# mbmc_io.net
KiCad netlist of a schematic drawn in EAGLE
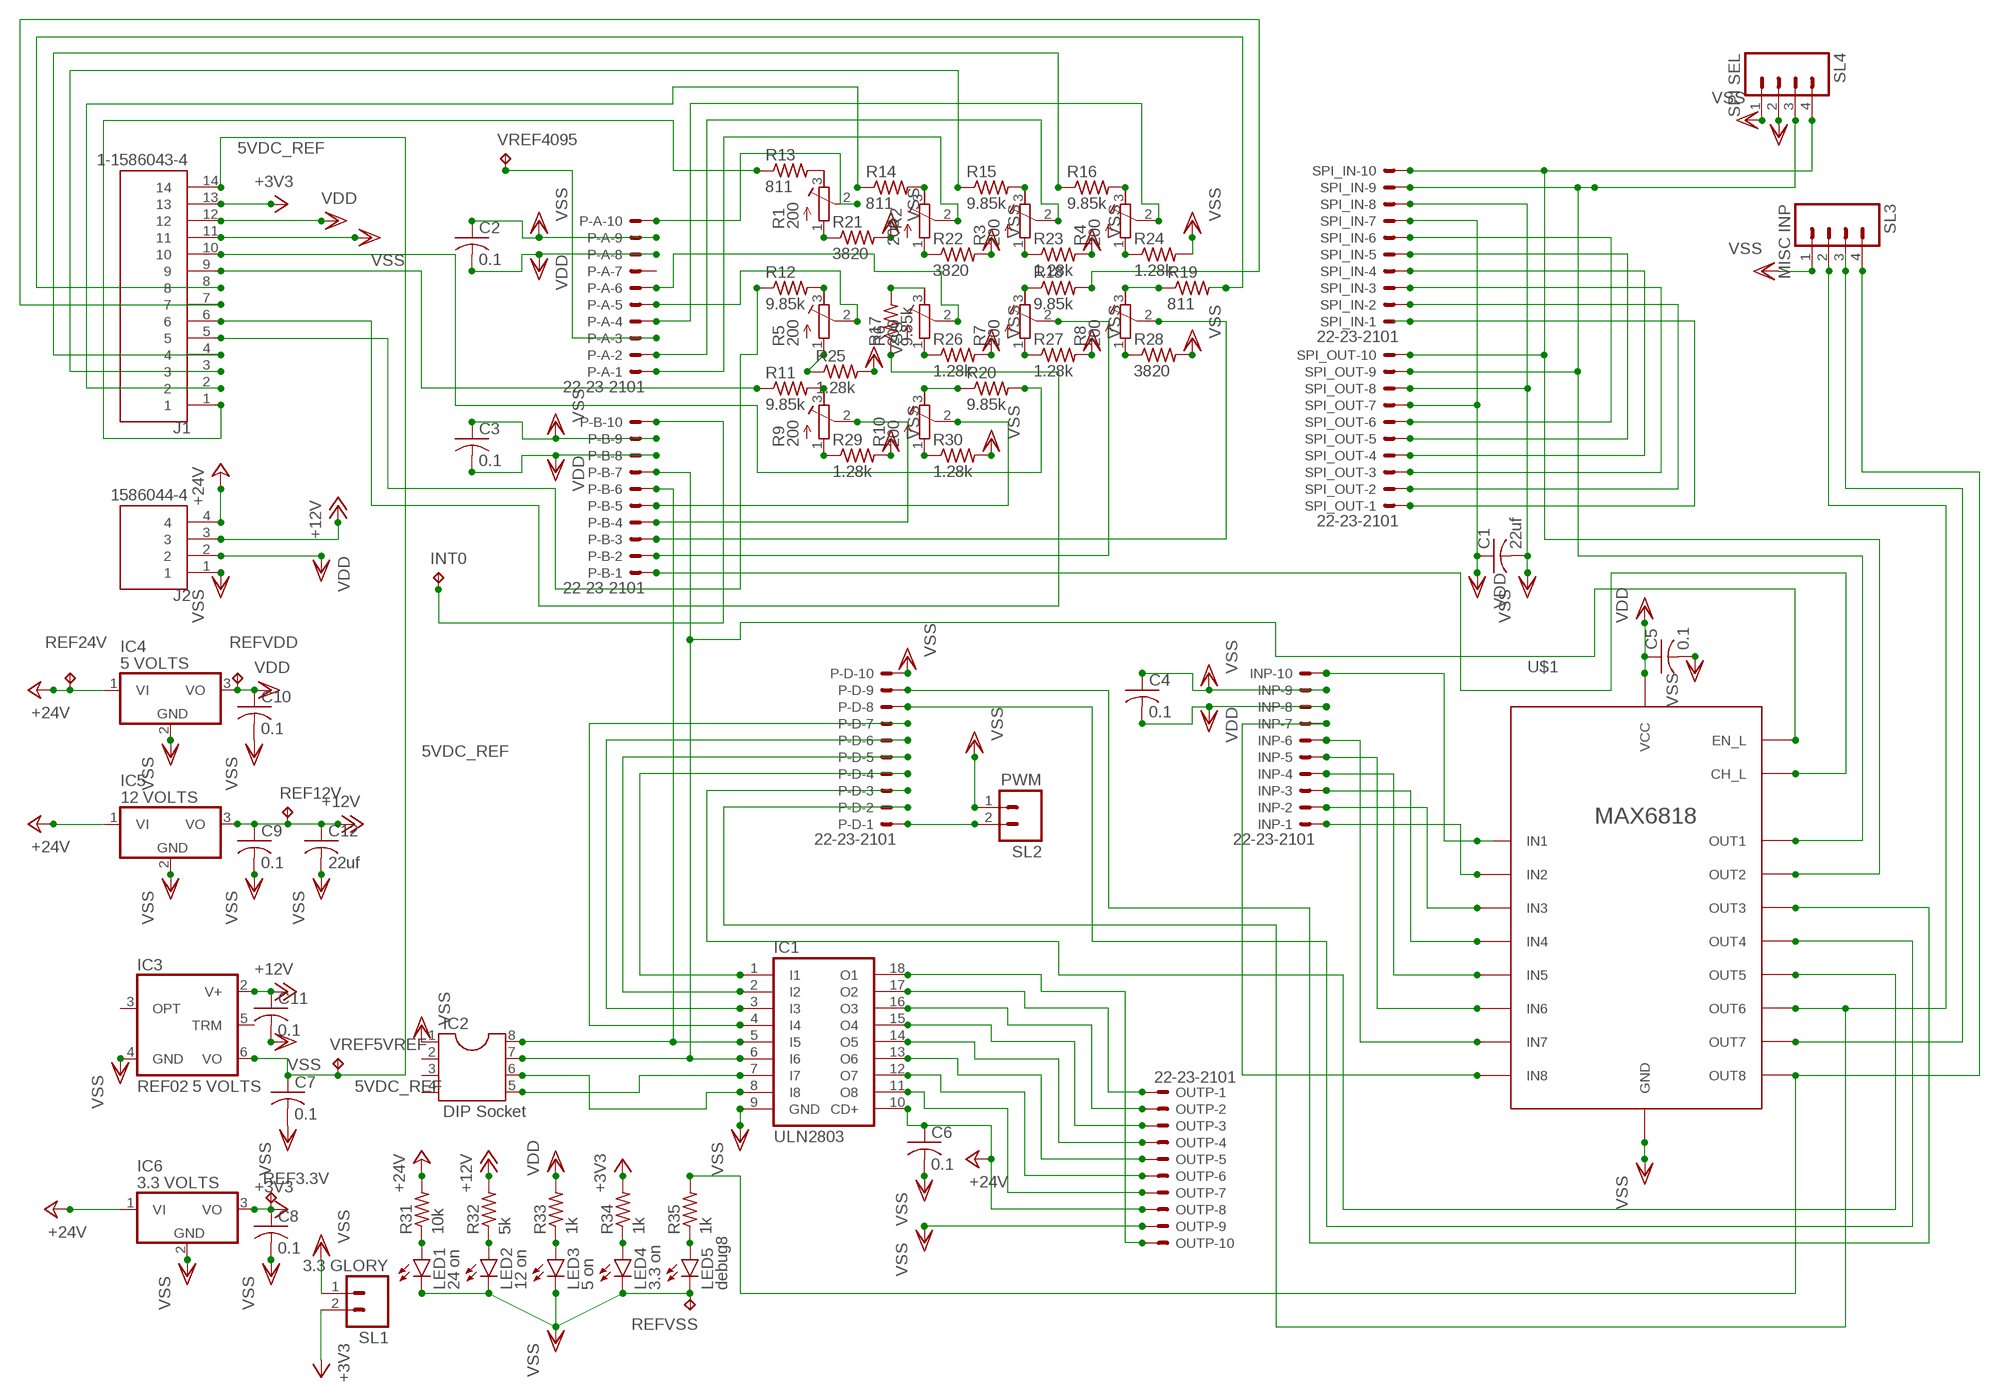
[diagram p0: schematic, sheet 1]

(export (version "E")
  (design (tool "Eeschema 10.0.6"))
  (components
    (comp (ref "C1")
      (value "22uf")
      (footprint "eagle-import:C0805")
      (libsource (lib "eagle-import") (part "C-USC0805"))
    )
    (comp (ref "C2")
      (value "0.1")
      (footprint "eagle-import:C0805")
      (libsource (lib "eagle-import") (part "C-USC0805"))
    )
    (comp (ref "C3")
      (value "0.1")
      (footprint "eagle-import:C0805")
      (libsource (lib "eagle-import") (part "C-USC0805"))
    )
    (comp (ref "C4")
      (value "0.1")
      (footprint "eagle-import:C0805")
      (libsource (lib "eagle-import") (part "C-USC0805"))
    )
    (comp (ref "C5")
      (value "0.1")
      (footprint "eagle-import:C0805")
      (libsource (lib "eagle-import") (part "C-USC0805"))
    )
    (comp (ref "C6")
      (value "0.1")
      (footprint "eagle-import:C0805")
      (libsource (lib "eagle-import") (part "C-USC0805"))
    )
    (comp (ref "C7")
      (value "0.1")
      (footprint "eagle-import:C0805")
      (libsource (lib "eagle-import") (part "C-USC0805"))
    )
    (comp (ref "C8")
      (value "0.1")
      (footprint "eagle-import:C0805")
      (libsource (lib "eagle-import") (part "C-USC0805"))
    )
    (comp (ref "C9")
      (value "0.1")
      (footprint "eagle-import:C0805")
      (libsource (lib "eagle-import") (part "C-USC0805"))
    )
    (comp (ref "C10")
      (value "0.1")
      (footprint "eagle-import:C0805")
      (libsource (lib "eagle-import") (part "C-USC0805"))
    )
    (comp (ref "C11")
      (value "0.1")
      (footprint "eagle-import:C0805")
      (libsource (lib "eagle-import") (part "C-USC0805"))
    )
    (comp (ref "C12")
      (value "22uf")
      (footprint "eagle-import:C0805")
      (libsource (lib "eagle-import") (part "C-USC0805"))
    )
    (comp (ref "IC1")
      (value "ULN2803")
      (footprint "eagle-import:DIL18")
      (libsource (lib "eagle-import") (part "ULN2803A"))
    )
    (comp (ref "IC2")
      (value "DIP Socket")
      (footprint "eagle-import:SOCKET-08")
      (libsource (lib "eagle-import") (part "DIL8S"))
    )
    (comp (ref "IC3")
      (value "REF02 5 VOLTS")
      (footprint "eagle-import:DIL08")
      (libsource (lib "eagle-import") (part "REF02Z"))
    )
    (comp (ref "IC4")
      (value "5 VOLTS")
      (footprint "eagle-import:TO220V")
      (libsource (lib "eagle-import") (part "78TV05"))
    )
    (comp (ref "IC5")
      (value "12 VOLTS")
      (footprint "eagle-import:TO220V")
      (libsource (lib "eagle-import") (part "78TV05"))
    )
    (comp (ref "IC6")
      (value "3.3 VOLTS")
      (footprint "eagle-import:TO220V")
      (libsource (lib "eagle-import") (part "78TV05"))
    )
    (comp (ref "INP")
      (value "22-23-2101")
      (footprint "eagle-import:22-23-2101")
      (fields (field (name "MF") "MOLEX"))
      (libsource (lib "eagle-import") (part "22-23-2101"))
    )
    (comp (ref "INT0")
      (value "TPB1,27")
      (footprint "eagle-import:B1,27")
      (libsource (lib "eagle-import") (part "TPB1,27"))
    )
    (comp (ref "J1")
      (value "1-1586043-4")
      (footprint "eagle-import:TE_1-1586043-4")
      (fields (field (name "MANUFACTURER") "TE"))
      (libsource (lib "eagle-import") (part "1-1586043-4"))
    )
    (comp (ref "J2")
      (value "1586044-4")
      (footprint "eagle-import:TE_1586044-4")
      (fields (field (name "MANUFACTURER") "TE"))
      (libsource (lib "eagle-import") (part "1586044-4"))
    )
    (comp (ref "LED1")
      (value "24 on")
      (footprint "eagle-import:CHIPLED_1206")
      (libsource (lib "eagle-import") (part "LEDCHIPLED_1206"))
    )
    (comp (ref "LED2")
      (value "12 on")
      (footprint "eagle-import:CHIPLED_1206")
      (libsource (lib "eagle-import") (part "LEDCHIPLED_1206"))
    )
    (comp (ref "LED3")
      (value "5 on")
      (footprint "eagle-import:CHIPLED_1206")
      (libsource (lib "eagle-import") (part "LEDCHIPLED_1206"))
    )
    (comp (ref "LED4")
      (value "3.3 on")
      (footprint "eagle-import:CHIPLED_1206")
      (libsource (lib "eagle-import") (part "LEDCHIPLED_1206"))
    )
    (comp (ref "LED5")
      (value "debug8")
      (footprint "eagle-import:CHIPLED_1206")
      (libsource (lib "eagle-import") (part "LEDCHIPLED_1206"))
    )
    (comp (ref "OUTP")
      (value "22-23-2101")
      (footprint "eagle-import:22-23-2101")
      (fields (field (name "MF") "MOLEX"))
      (libsource (lib "eagle-import") (part "22-23-2101"))
    )
    (comp (ref "P-A")
      (value "22-23-2101")
      (footprint "eagle-import:22-23-2101")
      (fields (field (name "MF") "MOLEX"))
      (libsource (lib "eagle-import") (part "22-23-2101"))
    )
    (comp (ref "P-B")
      (value "22-23-2101")
      (footprint "eagle-import:22-23-2101")
      (fields (field (name "MF") "MOLEX"))
      (libsource (lib "eagle-import") (part "22-23-2101"))
    )
    (comp (ref "P-D")
      (value "22-23-2101")
      (footprint "eagle-import:22-23-2101")
      (fields (field (name "MF") "MOLEX"))
      (libsource (lib "eagle-import") (part "22-23-2101"))
    )
    (comp (ref "R1")
      (value "200")
      (footprint "eagle-import:RTRIM3339P")
      (libsource (lib "eagle-import") (part "R-TRIMM3339P"))
    )
    (comp (ref "R2")
      (value "200")
      (footprint "eagle-import:RTRIM3339P")
      (libsource (lib "eagle-import") (part "R-TRIMM3339P"))
    )
    (comp (ref "R3")
      (value "200")
      (footprint "eagle-import:RTRIM3339P")
      (libsource (lib "eagle-import") (part "R-TRIMM3339P"))
    )
    (comp (ref "R4")
      (value "200")
      (footprint "eagle-import:RTRIM3339P")
      (libsource (lib "eagle-import") (part "R-TRIMM3339P"))
    )
    (comp (ref "R5")
      (value "200")
      (footprint "eagle-import:RTRIM3339P")
      (libsource (lib "eagle-import") (part "R-TRIMM3339P"))
    )
    (comp (ref "R6")
      (value "200")
      (footprint "eagle-import:RTRIM3339P")
      (libsource (lib "eagle-import") (part "R-TRIMM3339P"))
    )
    (comp (ref "R7")
      (value "200")
      (footprint "eagle-import:RTRIM3339P")
      (libsource (lib "eagle-import") (part "R-TRIMM3339P"))
    )
    (comp (ref "R8")
      (value "200")
      (footprint "eagle-import:RTRIM3339P")
      (libsource (lib "eagle-import") (part "R-TRIMM3339P"))
    )
    (comp (ref "R9")
      (value "200")
      (footprint "eagle-import:RTRIM3339P")
      (libsource (lib "eagle-import") (part "R-TRIMM3339P"))
    )
    (comp (ref "R10")
      (value "200")
      (footprint "eagle-import:RTRIM3339P")
      (libsource (lib "eagle-import") (part "R-TRIMM3339P"))
    )
    (comp (ref "R11")
      (value "9.85k")
      (footprint "eagle-import:R0805")
      (libsource (lib "eagle-import") (part "R-US_R0805"))
    )
    (comp (ref "R12")
      (value "9.85k")
      (footprint "eagle-import:R0805")
      (libsource (lib "eagle-import") (part "R-US_R0805"))
    )
    (comp (ref "R13")
      (value "811")
      (footprint "eagle-import:R0805")
      (libsource (lib "eagle-import") (part "R-US_R0805"))
    )
    (comp (ref "R14")
      (value "811")
      (footprint "eagle-import:R0805")
      (libsource (lib "eagle-import") (part "R-US_R0805"))
    )
    (comp (ref "R15")
      (value "9.85k")
      (footprint "eagle-import:R0805")
      (libsource (lib "eagle-import") (part "R-US_R0805"))
    )
    (comp (ref "R16")
      (value "9.85k")
      (footprint "eagle-import:R0805")
      (libsource (lib "eagle-import") (part "R-US_R0805"))
    )
    (comp (ref "R17")
      (value "9.85k")
      (footprint "eagle-import:R0805")
      (libsource (lib "eagle-import") (part "R-US_R0805"))
    )
    (comp (ref "R18")
      (value "9.85k")
      (footprint "eagle-import:R0805")
      (libsource (lib "eagle-import") (part "R-US_R0805"))
    )
    (comp (ref "R19")
      (value "811")
      (footprint "eagle-import:R0805")
      (libsource (lib "eagle-import") (part "R-US_R0805"))
    )
    (comp (ref "R20")
      (value "9.85k")
      (footprint "eagle-import:R0805")
      (libsource (lib "eagle-import") (part "R-US_R0805"))
    )
    (comp (ref "R21")
      (value "3820")
      (footprint "eagle-import:R0805")
      (libsource (lib "eagle-import") (part "R-US_R0805"))
    )
    (comp (ref "R22")
      (value "3820")
      (footprint "eagle-import:R0805")
      (libsource (lib "eagle-import") (part "R-US_R0805"))
    )
    (comp (ref "R23")
      (value "1.28k")
      (footprint "eagle-import:R0805")
      (libsource (lib "eagle-import") (part "R-US_R0805"))
    )
    (comp (ref "R24")
      (value "1.28k")
      (footprint "eagle-import:R0805")
      (libsource (lib "eagle-import") (part "R-US_R0805"))
    )
    (comp (ref "R25")
      (value "1.28k")
      (footprint "eagle-import:R0805")
      (libsource (lib "eagle-import") (part "R-US_R0805"))
    )
    (comp (ref "R26")
      (value "1.28k")
      (footprint "eagle-import:R0805")
      (libsource (lib "eagle-import") (part "R-US_R0805"))
    )
    (comp (ref "R27")
      (value "1.28k")
      (footprint "eagle-import:R0805")
      (libsource (lib "eagle-import") (part "R-US_R0805"))
    )
    (comp (ref "R28")
      (value "3820")
      (footprint "eagle-import:R0805")
      (libsource (lib "eagle-import") (part "R-US_R0805"))
    )
    (comp (ref "R29")
      (value "1.28k")
      (footprint "eagle-import:R0805")
      (libsource (lib "eagle-import") (part "R-US_R0805"))
    )
    (comp (ref "R30")
      (value "1.28k")
      (footprint "eagle-import:R0805")
      (libsource (lib "eagle-import") (part "R-US_R0805"))
    )
    (comp (ref "R31")
      (value "10k")
      (footprint "eagle-import:R0805")
      (libsource (lib "eagle-import") (part "R-US_R0805"))
    )
    (comp (ref "R32")
      (value "5k")
      (footprint "eagle-import:R0805")
      (libsource (lib "eagle-import") (part "R-US_R0805"))
    )
    (comp (ref "R33")
      (value "1k")
      (footprint "eagle-import:R0805")
      (libsource (lib "eagle-import") (part "R-US_R0805"))
    )
    (comp (ref "R34")
      (value "1k")
      (footprint "eagle-import:R0805")
      (libsource (lib "eagle-import") (part "R-US_R0805"))
    )
    (comp (ref "R35")
      (value "1k")
      (footprint "eagle-import:R0805")
      (libsource (lib "eagle-import") (part "R-US_R0805"))
    )
    (comp (ref "REF3.3V")
      (value "TPB1,27")
      (footprint "eagle-import:B1,27")
      (libsource (lib "eagle-import") (part "TPB1,27"))
    )
    (comp (ref "REF12V")
      (value "TPB1,27")
      (footprint "eagle-import:B1,27")
      (libsource (lib "eagle-import") (part "TPB1,27"))
    )
    (comp (ref "REF24V")
      (value "TPB1,27")
      (footprint "eagle-import:B1,27")
      (libsource (lib "eagle-import") (part "TPB1,27"))
    )
    (comp (ref "REFVDD")
      (value "TPB1,27")
      (footprint "eagle-import:B1,27")
      (libsource (lib "eagle-import") (part "TPB1,27"))
    )
    (comp (ref "REFVSS")
      (value "TPB1,27")
      (footprint "eagle-import:B1,27")
      (libsource (lib "eagle-import") (part "TPB1,27"))
    )
    (comp (ref "SL1")
      (value "3.3 GLORY")
      (footprint "eagle-import:02P")
      (libsource (lib "eagle-import") (part "M02"))
    )
    (comp (ref "SL2")
      (value "PWM")
      (footprint "eagle-import:02P")
      (libsource (lib "eagle-import") (part "M02"))
    )
    (comp (ref "SL3")
      (value "MISC INP")
      (footprint "eagle-import:04P")
      (libsource (lib "eagle-import") (part "M04"))
    )
    (comp (ref "SL4")
      (value "SPI SEL")
      (footprint "eagle-import:04P")
      (libsource (lib "eagle-import") (part "M04"))
    )
    (comp (ref "SPI_IN")
      (value "22-23-2101")
      (footprint "eagle-import:22-23-2101")
      (fields (field (name "MF") "MOLEX"))
      (libsource (lib "eagle-import") (part "22-23-2101"))
    )
    (comp (ref "SPI_OUT")
      (value "22-23-2101")
      (footprint "eagle-import:22-23-2101")
      (fields (field (name "MF") "MOLEX"))
      (libsource (lib "eagle-import") (part "22-23-2101"))
    )
    (comp (ref "U$1")
      (value "MAX6818")
      (footprint "eagle-import:SSOP20")
      (fields (field (name "MF") "Maxim Integrated"))
      (libsource (lib "eagle-import") (part "MAX6818"))
    )
    (comp (ref "VREF5VREF")
      (value "TPB1,27")
      (footprint "eagle-import:B1,27")
      (libsource (lib "eagle-import") (part "TPB1,27"))
    )
    (comp (ref "VREF4095")
      (value "TPB1,27")
      (footprint "eagle-import:B1,27")
      (libsource (lib "eagle-import") (part "TPB1,27"))
    )
  )
  (nets
    (net (code "1") (name "+3V3") (class "Default")
      (node (ref "C8") (pin "1") (pinfunction "1_1") (pintype "passive"))
      (node (ref "IC6") (pin "3") (pinfunction "VO_3") (pintype "passive"))
      (node (ref "J1") (pin "13") (pinfunction "13_13") (pintype "passive"))
      (node (ref "R34") (pin "2") (pinfunction "2_2") (pintype "passive"))
      (node (ref "REF3.3V") (pin "TP") (pinfunction "TP_TP") (pintype "input"))
      (node (ref "SL1") (pin "2") (pinfunction "2_2") (pintype "passive"))
    )
    (net (code "2") (name "+12V") (class "Default")
      (node (ref "C11") (pin "1") (pinfunction "1_1") (pintype "passive"))
      (node (ref "C12") (pin "1") (pinfunction "1_1") (pintype "passive"))
      (node (ref "C9") (pin "1") (pinfunction "1_1") (pintype "passive"))
      (node (ref "IC3") (pin "2") (pinfunction "V+_2") (pintype "power_in"))
      (node (ref "IC5") (pin "3") (pinfunction "VO_3") (pintype "passive"))
      (node (ref "J2") (pin "3") (pinfunction "3_3") (pintype "passive"))
      (node (ref "R32") (pin "2") (pinfunction "2_2") (pintype "passive"))
      (node (ref "REF12V") (pin "TP") (pinfunction "TP_TP") (pintype "input"))
    )
    (net (code "3") (name "+24V") (class "Default")
      (node (ref "C6") (pin "1") (pinfunction "1_1") (pintype "passive"))
      (node (ref "IC1") (pin "10") (pinfunction "CD+_10") (pintype "passive"))
      (node (ref "IC4") (pin "1") (pinfunction "VI_1") (pintype "input"))
      (node (ref "IC5") (pin "1") (pinfunction "VI_1") (pintype "input"))
      (node (ref "IC6") (pin "1") (pinfunction "VI_1") (pintype "input"))
      (node (ref "J2") (pin "4") (pinfunction "4_4") (pintype "passive"))
      (node (ref "OUTP") (pin "8") (pinfunction "S_8") (pintype "passive"))
      (node (ref "R31") (pin "2") (pinfunction "2_2") (pintype "passive"))
      (node (ref "REF24V") (pin "TP") (pinfunction "TP_TP") (pintype "input"))
    )
    (net (code "4") (name "/5VDC_REF") (class "Default")
      (node (ref "C7") (pin "1") (pinfunction "1_1") (pintype "passive"))
      (node (ref "IC3") (pin "6") (pinfunction "VO_6") (pintype "output"))
      (node (ref "J1") (pin "14") (pinfunction "14_14") (pintype "passive"))
      (node (ref "VREF5VREF") (pin "TP") (pinfunction "TP_TP") (pintype "input"))
    )
    (net (code "5") (name "Net-(IC1-I1)") (class "Default")
      (node (ref "IC1") (pin "1") (pinfunction "I1_1") (pintype "input"))
      (node (ref "P-D") (pin "4") (pinfunction "S_4") (pintype "passive"))
    )
    (net (code "6") (name "Net-(IC1-I2)") (class "Default")
      (node (ref "IC1") (pin "2") (pinfunction "I2_2") (pintype "input"))
      (node (ref "P-D") (pin "5") (pinfunction "S_5") (pintype "passive"))
    )
    (net (code "7") (name "Net-(IC1-I3)") (class "Default")
      (node (ref "IC1") (pin "3") (pinfunction "I3_3") (pintype "input"))
      (node (ref "P-D") (pin "6") (pinfunction "S_6") (pintype "passive"))
    )
    (net (code "8") (name "Net-(IC1-I4)") (class "Default")
      (node (ref "IC1") (pin "4") (pinfunction "I4_4") (pintype "input"))
      (node (ref "P-D") (pin "7") (pinfunction "S_7") (pintype "passive"))
    )
    (net (code "9") (name "Net-(IC1-I5)") (class "Default")
      (node (ref "IC1") (pin "5") (pinfunction "I5_5") (pintype "input"))
      (node (ref "IC2") (pin "8") (pinfunction "8_8") (pintype "passive"))
      (node (ref "P-B") (pin "6") (pinfunction "S_6") (pintype "passive"))
    )
    (net (code "10") (name "Net-(IC1-I6)") (class "Default")
      (node (ref "IC1") (pin "6") (pinfunction "I6_6") (pintype "input"))
      (node (ref "IC2") (pin "7") (pinfunction "7_7") (pintype "passive"))
      (node (ref "P-B") (pin "7") (pinfunction "S_7") (pintype "passive"))
      (node (ref "U$1") (pin "EN_L") (pinfunction "EN_L_EN_L") (pintype "bidirectional"))
    )
    (net (code "11") (name "Net-(IC1-I7)") (class "Default")
      (node (ref "IC1") (pin "7") (pinfunction "I7_7") (pintype "input"))
      (node (ref "IC2") (pin "5") (pinfunction "5_5") (pintype "passive"))
    )
    (net (code "12") (name "Net-(IC1-I8)") (class "Default")
      (node (ref "IC1") (pin "8") (pinfunction "I8_8") (pintype "input"))
      (node (ref "IC2") (pin "6") (pinfunction "6_6") (pintype "passive"))
    )
    (net (code "13") (name "Net-(IC1-O1)") (class "Default")
      (node (ref "IC1") (pin "18") (pinfunction "O1_18") (pintype "open_collector"))
      (node (ref "OUTP") (pin "10") (pinfunction "S_10") (pintype "passive"))
    )
    (net (code "14") (name "Net-(IC1-O2)") (class "Default")
      (node (ref "IC1") (pin "17") (pinfunction "O2_17") (pintype "open_collector"))
      (node (ref "OUTP") (pin "1") (pinfunction "S_1") (pintype "passive"))
    )
    (net (code "15") (name "Net-(IC1-O3)") (class "Default")
      (node (ref "IC1") (pin "16") (pinfunction "O3_16") (pintype "open_collector"))
      (node (ref "OUTP") (pin "2") (pinfunction "S_2") (pintype "passive"))
    )
    (net (code "16") (name "Net-(IC1-O4)") (class "Default")
      (node (ref "IC1") (pin "15") (pinfunction "O4_15") (pintype "open_collector"))
      (node (ref "OUTP") (pin "3") (pinfunction "S_3") (pintype "passive"))
    )
    (net (code "17") (name "Net-(IC1-O5)") (class "Default")
      (node (ref "IC1") (pin "14") (pinfunction "O5_14") (pintype "open_collector"))
      (node (ref "OUTP") (pin "4") (pinfunction "S_4") (pintype "passive"))
    )
    (net (code "18") (name "Net-(IC1-O6)") (class "Default")
      (node (ref "IC1") (pin "13") (pinfunction "O6_13") (pintype "open_collector"))
      (node (ref "OUTP") (pin "5") (pinfunction "S_5") (pintype "passive"))
    )
    (net (code "19") (name "Net-(IC1-O7)") (class "Default")
      (node (ref "IC1") (pin "12") (pinfunction "O7_12") (pintype "open_collector"))
      (node (ref "OUTP") (pin "6") (pinfunction "S_6") (pintype "passive"))
    )
    (net (code "20") (name "Net-(IC1-O8)") (class "Default")
      (node (ref "IC1") (pin "11") (pinfunction "O8_11") (pintype "open_collector"))
      (node (ref "OUTP") (pin "7") (pinfunction "S_7") (pintype "passive"))
    )
    (net (code "21") (name "Net-(INPA-S)") (class "Default")
      (node (ref "INP") (pin "1") (pinfunction "S_1") (pintype "passive"))
      (node (ref "U$1") (pin "IN2") (pinfunction "IN2_IN2") (pintype "bidirectional"))
    )
    (net (code "22") (name "Net-(INPB-S)") (class "Default")
      (node (ref "INP") (pin "10") (pinfunction "S_10") (pintype "passive"))
      (node (ref "U$1") (pin "IN1") (pinfunction "IN1_IN1") (pintype "bidirectional"))
    )
    (net (code "23") (name "Net-(INPC-S)") (class "Default")
      (node (ref "INP") (pin "2") (pinfunction "S_2") (pintype "passive"))
      (node (ref "U$1") (pin "IN3") (pinfunction "IN3_IN3") (pintype "bidirectional"))
    )
    (net (code "24") (name "Net-(INPD-S)") (class "Default")
      (node (ref "INP") (pin "3") (pinfunction "S_3") (pintype "passive"))
      (node (ref "U$1") (pin "IN4") (pinfunction "IN4_IN4") (pintype "bidirectional"))
    )
    (net (code "25") (name "Net-(INPE-S)") (class "Default")
      (node (ref "INP") (pin "4") (pinfunction "S_4") (pintype "passive"))
      (node (ref "U$1") (pin "IN5") (pinfunction "IN5_IN5") (pintype "bidirectional"))
    )
    (net (code "26") (name "Net-(INPF-S)") (class "Default")
      (node (ref "INP") (pin "5") (pinfunction "S_5") (pintype "passive"))
      (node (ref "U$1") (pin "IN6") (pinfunction "IN6_IN6") (pintype "bidirectional"))
    )
    (net (code "27") (name "Net-(INPG-S)") (class "Default")
      (node (ref "INP") (pin "6") (pinfunction "S_6") (pintype "passive"))
      (node (ref "U$1") (pin "IN7") (pinfunction "IN7_IN7") (pintype "bidirectional"))
    )
    (net (code "28") (name "Net-(INPH-S)") (class "Default")
      (node (ref "INP") (pin "7") (pinfunction "S_7") (pintype "passive"))
      (node (ref "U$1") (pin "IN8") (pinfunction "IN8_IN8") (pintype "bidirectional"))
    )
    (net (code "29") (name "Net-(J1-Pad1)") (class "Default")
      (node (ref "J1") (pin "1") (pinfunction "1_1") (pintype "passive"))
      (node (ref "R13") (pin "1") (pinfunction "1_1") (pintype "passive"))
    )
    (net (code "30") (name "Net-(J1-Pad2)") (class "Default")
      (node (ref "J1") (pin "2") (pinfunction "2_2") (pintype "passive"))
      (node (ref "R14") (pin "1") (pinfunction "1_1") (pintype "passive"))
    )
    (net (code "31") (name "Net-(J1-Pad3)") (class "Default")
      (node (ref "J1") (pin "3") (pinfunction "3_3") (pintype "passive"))
      (node (ref "R15") (pin "1") (pinfunction "1_1") (pintype "passive"))
    )
    (net (code "32") (name "Net-(J1-Pad4)") (class "Default")
      (node (ref "J1") (pin "4") (pinfunction "4_4") (pintype "passive"))
      (node (ref "R16") (pin "1") (pinfunction "1_1") (pintype "passive"))
    )
    (net (code "33") (name "Net-(J1-Pad5)") (class "Default")
      (node (ref "J1") (pin "5") (pinfunction "5_5") (pintype "passive"))
      (node (ref "R12") (pin "1") (pinfunction "1_1") (pintype "passive"))
    )
    (net (code "34") (name "Net-(J1-Pad6)") (class "Default")
      (node (ref "J1") (pin "6") (pinfunction "6_6") (pintype "passive"))
      (node (ref "R17") (pin "1") (pinfunction "1_1") (pintype "passive"))
    )
    (net (code "35") (name "Net-(J1-Pad7)") (class "Default")
      (node (ref "J1") (pin "7") (pinfunction "7_7") (pintype "passive"))
      (node (ref "R18") (pin "2") (pinfunction "2_2") (pintype "passive"))
    )
    (net (code "36") (name "Net-(J1-Pad8)") (class "Default")
      (node (ref "J1") (pin "8") (pinfunction "8_8") (pintype "passive"))
      (node (ref "R19") (pin "2") (pinfunction "2_2") (pintype "passive"))
    )
    (net (code "37") (name "Net-(J1-Pad9)") (class "Default")
      (node (ref "J1") (pin "9") (pinfunction "9_9") (pintype "passive"))
      (node (ref "R11") (pin "1") (pinfunction "1_1") (pintype "passive"))
    )
    (net (code "38") (name "Net-(J1-Pad10)") (class "Default")
      (node (ref "J1") (pin "10") (pinfunction "10_10") (pintype "passive"))
      (node (ref "R20") (pin "2") (pinfunction "2_2") (pintype "passive"))
    )
    (net (code "39") (name "Net-(LED1-PadA)") (class "Default")
      (node (ref "LED1") (pin "A") (pinfunction "A_A") (pintype "passive"))
      (node (ref "R31") (pin "1") (pinfunction "1_1") (pintype "passive"))
    )
    (net (code "40") (name "Net-(LED2-PadA)") (class "Default")
      (node (ref "LED2") (pin "A") (pinfunction "A_A") (pintype "passive"))
      (node (ref "R32") (pin "1") (pinfunction "1_1") (pintype "passive"))
    )
    (net (code "41") (name "Net-(LED3-PadA)") (class "Default")
      (node (ref "LED3") (pin "A") (pinfunction "A_A") (pintype "passive"))
      (node (ref "R33") (pin "1") (pinfunction "1_1") (pintype "passive"))
    )
    (net (code "42") (name "Net-(LED4-PadA)") (class "Default")
      (node (ref "LED4") (pin "A") (pinfunction "A_A") (pintype "passive"))
      (node (ref "R34") (pin "1") (pinfunction "1_1") (pintype "passive"))
    )
    (net (code "43") (name "Net-(LED5-PadA)") (class "Default")
      (node (ref "LED5") (pin "A") (pinfunction "A_A") (pintype "passive"))
      (node (ref "R35") (pin "1") (pinfunction "1_1") (pintype "passive"))
    )
    (net (code "44") (name "Net-(P-AA-S)") (class "Default")
      (node (ref "P-A") (pin "1") (pinfunction "S_1") (pintype "passive"))
      (node (ref "R2") (pin "2") (pinfunction "S_2") (pintype "passive"))
    )
    (net (code "45") (name "Net-(P-AB-S)") (class "Default")
      (node (ref "P-A") (pin "10") (pinfunction "S_10") (pintype "passive"))
      (node (ref "R1") (pin "2") (pinfunction "S_2") (pintype "passive"))
    )
    (net (code "46") (name "Net-(P-AC-S)") (class "Default")
      (node (ref "P-A") (pin "2") (pinfunction "S_2") (pintype "passive"))
      (node (ref "R3") (pin "2") (pinfunction "S_2") (pintype "passive"))
    )
    (net (code "47") (name "Net-(P-AD-S)") (class "Default")
      (node (ref "P-A") (pin "3") (pinfunction "S_3") (pintype "passive"))
      (node (ref "VREF4095") (pin "TP") (pinfunction "TP_TP") (pintype "input"))
    )
    (net (code "48") (name "Net-(P-AE-S)") (class "Default")
      (node (ref "P-A") (pin "4") (pinfunction "S_4") (pintype "passive"))
      (node (ref "R4") (pin "2") (pinfunction "S_2") (pintype "passive"))
    )
    (net (code "49") (name "Net-(P-AF-S)") (class "Default")
      (node (ref "P-A") (pin "5") (pinfunction "S_5") (pintype "passive"))
      (node (ref "R5") (pin "2") (pinfunction "S_2") (pintype "passive"))
    )
    (net (code "50") (name "Net-(P-AG-S)") (class "Default")
      (node (ref "P-A") (pin "6") (pinfunction "S_6") (pintype "passive"))
      (node (ref "R6") (pin "2") (pinfunction "S_2") (pintype "passive"))
    )
    (net (code "51") (name "Net-(P-BA-S)") (class "Default")
      (node (ref "P-B") (pin "1") (pinfunction "S_1") (pintype "passive"))
      (node (ref "U$1") (pin "CH_L") (pinfunction "CH_L_CH_L") (pintype "bidirectional"))
    )
    (net (code "52") (name "Net-(P-BB-S)") (class "Default")
      (node (ref "INT0") (pin "TP") (pinfunction "TP_TP") (pintype "input"))
      (node (ref "P-B") (pin "10") (pinfunction "S_10") (pintype "passive"))
    )
    (net (code "53") (name "Net-(P-BC-S)") (class "Default")
      (node (ref "P-B") (pin "2") (pinfunction "S_2") (pintype "passive"))
      (node (ref "R7") (pin "2") (pinfunction "S_2") (pintype "passive"))
    )
    (net (code "54") (name "Net-(P-BD-S)") (class "Default")
      (node (ref "P-B") (pin "3") (pinfunction "S_3") (pintype "passive"))
      (node (ref "R8") (pin "2") (pinfunction "S_2") (pintype "passive"))
    )
    (net (code "55") (name "Net-(P-BE-S)") (class "Default")
      (node (ref "P-B") (pin "4") (pinfunction "S_4") (pintype "passive"))
      (node (ref "R9") (pin "2") (pinfunction "S_2") (pintype "passive"))
    )
    (net (code "56") (name "Net-(P-BF-S)") (class "Default")
      (node (ref "P-B") (pin "5") (pinfunction "S_5") (pintype "passive"))
      (node (ref "R10") (pin "2") (pinfunction "S_2") (pintype "passive"))
    )
    (net (code "57") (name "Net-(P-DA-S)") (class "Default")
      (node (ref "P-D") (pin "1") (pinfunction "S_1") (pintype "passive"))
      (node (ref "SL2") (pin "2") (pinfunction "2_2") (pintype "passive"))
    )
    (net (code "58") (name "Net-(P-DC-S)") (class "Default")
      (node (ref "P-D") (pin "2") (pinfunction "S_2") (pintype "passive"))
      (node (ref "SL3") (pin "2") (pinfunction "2_2") (pintype "passive"))
      (node (ref "U$1") (pin "OUT6") (pinfunction "OUT6_OUT6") (pintype "bidirectional"))
    )
    (net (code "59") (name "Net-(P-DD-S)") (class "Default")
      (node (ref "P-D") (pin "3") (pinfunction "S_3") (pintype "passive"))
      (node (ref "U$1") (pin "OUT5") (pinfunction "OUT5_OUT5") (pintype "bidirectional"))
    )
    (net (code "60") (name "Net-(P-DI-S)") (class "Default")
      (node (ref "P-D") (pin "8") (pinfunction "S_8") (pintype "passive"))
      (node (ref "U$1") (pin "OUT4") (pinfunction "OUT4_OUT4") (pintype "bidirectional"))
    )
    (net (code "61") (name "Net-(P-DJ-S)") (class "Default")
      (node (ref "P-D") (pin "9") (pinfunction "S_9") (pintype "passive"))
      (node (ref "U$1") (pin "OUT3") (pinfunction "OUT3_OUT3") (pintype "bidirectional"))
    )
    (net (code "62") (name "Net-(R1-A)") (class "Default")
      (node (ref "R1") (pin "1") (pinfunction "A_1") (pintype "passive"))
      (node (ref "R21") (pin "1") (pinfunction "1_1") (pintype "passive"))
    )
    (net (code "63") (name "Net-(R1-E)") (class "Default")
      (node (ref "R1") (pin "3") (pinfunction "E_3") (pintype "passive"))
      (node (ref "R13") (pin "2") (pinfunction "2_2") (pintype "passive"))
    )
    (net (code "64") (name "Net-(R2-A)") (class "Default")
      (node (ref "R2") (pin "1") (pinfunction "A_1") (pintype "passive"))
      (node (ref "R22") (pin "1") (pinfunction "1_1") (pintype "passive"))
    )
    (net (code "65") (name "Net-(R2-E)") (class "Default")
      (node (ref "R14") (pin "2") (pinfunction "2_2") (pintype "passive"))
      (node (ref "R2") (pin "3") (pinfunction "E_3") (pintype "passive"))
    )
    (net (code "66") (name "Net-(R3-A)") (class "Default")
      (node (ref "R23") (pin "1") (pinfunction "1_1") (pintype "passive"))
      (node (ref "R3") (pin "1") (pinfunction "A_1") (pintype "passive"))
    )
    (net (code "67") (name "Net-(R3-E)") (class "Default")
      (node (ref "R15") (pin "2") (pinfunction "2_2") (pintype "passive"))
      (node (ref "R3") (pin "3") (pinfunction "E_3") (pintype "passive"))
    )
    (net (code "68") (name "Net-(R4-A)") (class "Default")
      (node (ref "R24") (pin "1") (pinfunction "1_1") (pintype "passive"))
      (node (ref "R4") (pin "1") (pinfunction "A_1") (pintype "passive"))
    )
    (net (code "69") (name "Net-(R4-E)") (class "Default")
      (node (ref "R16") (pin "2") (pinfunction "2_2") (pintype "passive"))
      (node (ref "R4") (pin "3") (pinfunction "E_3") (pintype "passive"))
    )
    (net (code "70") (name "Net-(R5-A)") (class "Default")
      (node (ref "R25") (pin "1") (pinfunction "1_1") (pintype "passive"))
      (node (ref "R5") (pin "1") (pinfunction "A_1") (pintype "passive"))
    )
    (net (code "71") (name "Net-(R5-E)") (class "Default")
      (node (ref "R12") (pin "2") (pinfunction "2_2") (pintype "passive"))
      (node (ref "R5") (pin "3") (pinfunction "E_3") (pintype "passive"))
    )
    (net (code "72") (name "Net-(R6-A)") (class "Default")
      (node (ref "R26") (pin "1") (pinfunction "1_1") (pintype "passive"))
      (node (ref "R6") (pin "1") (pinfunction "A_1") (pintype "passive"))
    )
    (net (code "73") (name "Net-(R6-E)") (class "Default")
      (node (ref "R17") (pin "2") (pinfunction "2_2") (pintype "passive"))
      (node (ref "R6") (pin "3") (pinfunction "E_3") (pintype "passive"))
    )
    (net (code "74") (name "Net-(R7-A)") (class "Default")
      (node (ref "R27") (pin "1") (pinfunction "1_1") (pintype "passive"))
      (node (ref "R7") (pin "1") (pinfunction "A_1") (pintype "passive"))
    )
    (net (code "75") (name "Net-(R7-E)") (class "Default")
      (node (ref "R18") (pin "1") (pinfunction "1_1") (pintype "passive"))
      (node (ref "R7") (pin "3") (pinfunction "E_3") (pintype "passive"))
    )
    (net (code "76") (name "Net-(R8-A)") (class "Default")
      (node (ref "R28") (pin "1") (pinfunction "1_1") (pintype "passive"))
      (node (ref "R8") (pin "1") (pinfunction "A_1") (pintype "passive"))
    )
    (net (code "77") (name "Net-(R8-E)") (class "Default")
      (node (ref "R19") (pin "1") (pinfunction "1_1") (pintype "passive"))
      (node (ref "R8") (pin "3") (pinfunction "E_3") (pintype "passive"))
    )
    (net (code "78") (name "Net-(R9-A)") (class "Default")
      (node (ref "R29") (pin "1") (pinfunction "1_1") (pintype "passive"))
      (node (ref "R9") (pin "1") (pinfunction "A_1") (pintype "passive"))
    )
    (net (code "79") (name "Net-(R9-E)") (class "Default")
      (node (ref "R11") (pin "2") (pinfunction "2_2") (pintype "passive"))
      (node (ref "R9") (pin "3") (pinfunction "E_3") (pintype "passive"))
    )
    (net (code "80") (name "Net-(R10-A)") (class "Default")
      (node (ref "R10") (pin "1") (pinfunction "A_1") (pintype "passive"))
      (node (ref "R30") (pin "1") (pinfunction "1_1") (pintype "passive"))
    )
    (net (code "81") (name "Net-(R10-E)") (class "Default")
      (node (ref "R10") (pin "3") (pinfunction "E_3") (pintype "passive"))
      (node (ref "R20") (pin "1") (pinfunction "1_1") (pintype "passive"))
    )
    (net (code "82") (name "Net-(R35-Pad2)") (class "Default")
      (node (ref "R35") (pin "2") (pinfunction "2_2") (pintype "passive"))
      (node (ref "SL3") (pin "4") (pinfunction "4_4") (pintype "passive"))
      (node (ref "U$1") (pin "OUT8") (pinfunction "OUT8_OUT8") (pintype "bidirectional"))
    )
    (net (code "83") (name "Net-(SL3-Pad3)") (class "Default")
      (node (ref "SL3") (pin "3") (pinfunction "3_3") (pintype "passive"))
      (node (ref "U$1") (pin "OUT7") (pinfunction "OUT7_OUT7") (pintype "bidirectional"))
    )
    (net (code "84") (name "Net-(SPI_INA-S)") (class "Default")
      (node (ref "SPI_IN") (pin "1") (pinfunction "S_1") (pintype "passive"))
      (node (ref "SPI_OUT") (pin "1") (pinfunction "S_1") (pintype "passive"))
    )
    (net (code "85") (name "Net-(SPI_INB-S)") (class "Default")
      (node (ref "SL4") (pin "4") (pinfunction "4_4") (pintype "passive"))
      (node (ref "SPI_IN") (pin "10") (pinfunction "S_10") (pintype "passive"))
      (node (ref "SPI_OUT") (pin "10") (pinfunction "S_10") (pintype "passive"))
      (node (ref "U$1") (pin "OUT2") (pinfunction "OUT2_OUT2") (pintype "bidirectional"))
    )
    (net (code "86") (name "Net-(SPI_INC-S)") (class "Default")
      (node (ref "SPI_IN") (pin "2") (pinfunction "S_2") (pintype "passive"))
      (node (ref "SPI_OUT") (pin "2") (pinfunction "S_2") (pintype "passive"))
    )
    (net (code "87") (name "Net-(SPI_IND-S)") (class "Default")
      (node (ref "SPI_IN") (pin "3") (pinfunction "S_3") (pintype "passive"))
      (node (ref "SPI_OUT") (pin "3") (pinfunction "S_3") (pintype "passive"))
    )
    (net (code "88") (name "Net-(SPI_INE-S)") (class "Default")
      (node (ref "SPI_IN") (pin "4") (pinfunction "S_4") (pintype "passive"))
      (node (ref "SPI_OUT") (pin "4") (pinfunction "S_4") (pintype "passive"))
    )
    (net (code "89") (name "Net-(SPI_INF-S)") (class "Default")
      (node (ref "SPI_IN") (pin "5") (pinfunction "S_5") (pintype "passive"))
      (node (ref "SPI_OUT") (pin "5") (pinfunction "S_5") (pintype "passive"))
    )
    (net (code "90") (name "Net-(SPI_ING-S)") (class "Default")
      (node (ref "SPI_IN") (pin "6") (pinfunction "S_6") (pintype "passive"))
      (node (ref "SPI_OUT") (pin "6") (pinfunction "S_6") (pintype "passive"))
    )
    (net (code "91") (name "Net-(SPI_INJ-S)") (class "Default")
      (node (ref "SL4") (pin "3") (pinfunction "3_3") (pintype "passive"))
      (node (ref "SPI_IN") (pin "9") (pinfunction "S_9") (pintype "passive"))
      (node (ref "SPI_OUT") (pin "9") (pinfunction "S_9") (pintype "passive"))
      (node (ref "U$1") (pin "OUT1") (pinfunction "OUT1_OUT1") (pintype "bidirectional"))
    )
    (net (code "92") (name "VDD") (class "Default")
      (node (ref "C1") (pin "1") (pinfunction "1_1") (pintype "passive"))
      (node (ref "C10") (pin "1") (pinfunction "1_1") (pintype "passive"))
      (node (ref "C2") (pin "2") (pinfunction "2_2") (pintype "passive"))
      (node (ref "C3") (pin "2") (pinfunction "2_2") (pintype "passive"))
      (node (ref "C4") (pin "2") (pinfunction "2_2") (pintype "passive"))
      (node (ref "C5") (pin "1") (pinfunction "1_1") (pintype "passive"))
      (node (ref "IC4") (pin "3") (pinfunction "VO_3") (pintype "passive"))
      (node (ref "INP") (pin "8") (pinfunction "S_8") (pintype "passive"))
      (node (ref "J1") (pin "12") (pinfunction "12_12") (pintype "passive"))
      (node (ref "J2") (pin "2") (pinfunction "2_2") (pintype "passive"))
      (node (ref "P-A") (pin "8") (pinfunction "S_8") (pintype "passive"))
      (node (ref "P-B") (pin "8") (pinfunction "S_8") (pintype "passive"))
      (node (ref "R33") (pin "2") (pinfunction "2_2") (pintype "passive"))
      (node (ref "REFVDD") (pin "TP") (pinfunction "TP_TP") (pintype "input"))
      (node (ref "SL4") (pin "2") (pinfunction "2_2") (pintype "passive"))
      (node (ref "SPI_IN") (pin "7") (pinfunction "S_7") (pintype "passive"))
      (node (ref "SPI_OUT") (pin "7") (pinfunction "S_7") (pintype "passive"))
      (node (ref "U$1") (pin "VCC") (pinfunction "VCC_VCC") (pintype "bidirectional"))
    )
    (net (code "93") (name "VSS") (class "Default")
      (node (ref "C1") (pin "2") (pinfunction "2_2") (pintype "passive"))
      (node (ref "C10") (pin "2") (pinfunction "2_2") (pintype "passive"))
      (node (ref "C11") (pin "2") (pinfunction "2_2") (pintype "passive"))
      (node (ref "C12") (pin "2") (pinfunction "2_2") (pintype "passive"))
      (node (ref "C2") (pin "1") (pinfunction "1_1") (pintype "passive"))
      (node (ref "C3") (pin "1") (pinfunction "1_1") (pintype "passive"))
      (node (ref "C4") (pin "1") (pinfunction "1_1") (pintype "passive"))
      (node (ref "C5") (pin "2") (pinfunction "2_2") (pintype "passive"))
      (node (ref "C6") (pin "2") (pinfunction "2_2") (pintype "passive"))
      (node (ref "C7") (pin "2") (pinfunction "2_2") (pintype "passive"))
      (node (ref "C8") (pin "2") (pinfunction "2_2") (pintype "passive"))
      (node (ref "C9") (pin "2") (pinfunction "2_2") (pintype "passive"))
      (node (ref "IC1") (pin "9") (pinfunction "GND_9") (pintype "power_in"))
      (node (ref "IC2") (pin "1") (pinfunction "1_1") (pintype "passive"))
      (node (ref "IC3") (pin "4") (pinfunction "GND_4") (pintype "power_in"))
      (node (ref "IC4") (pin "2") (pinfunction "GND_2") (pintype "passive"))
      (node (ref "IC5") (pin "2") (pinfunction "GND_2") (pintype "passive"))
      (node (ref "IC6") (pin "2") (pinfunction "GND_2") (pintype "passive"))
      (node (ref "INP") (pin "9") (pinfunction "S_9") (pintype "passive"))
      (node (ref "J1") (pin "11") (pinfunction "11_11") (pintype "passive"))
      (node (ref "J2") (pin "1") (pinfunction "1_1") (pintype "passive"))
      (node (ref "LED1") (pin "C") (pinfunction "C_C") (pintype "passive"))
      (node (ref "LED2") (pin "C") (pinfunction "C_C") (pintype "passive"))
      (node (ref "LED3") (pin "C") (pinfunction "C_C") (pintype "passive"))
      (node (ref "LED4") (pin "C") (pinfunction "C_C") (pintype "passive"))
      (node (ref "LED5") (pin "C") (pinfunction "C_C") (pintype "passive"))
      (node (ref "OUTP") (pin "9") (pinfunction "S_9") (pintype "passive"))
      (node (ref "P-A") (pin "9") (pinfunction "S_9") (pintype "passive"))
      (node (ref "P-B") (pin "9") (pinfunction "S_9") (pintype "passive"))
      (node (ref "P-D") (pin "10") (pinfunction "S_10") (pintype "passive"))
      (node (ref "R21") (pin "2") (pinfunction "2_2") (pintype "passive"))
      (node (ref "R22") (pin "2") (pinfunction "2_2") (pintype "passive"))
      (node (ref "R23") (pin "2") (pinfunction "2_2") (pintype "passive"))
      (node (ref "R24") (pin "2") (pinfunction "2_2") (pintype "passive"))
      (node (ref "R25") (pin "2") (pinfunction "2_2") (pintype "passive"))
      (node (ref "R26") (pin "2") (pinfunction "2_2") (pintype "passive"))
      (node (ref "R27") (pin "2") (pinfunction "2_2") (pintype "passive"))
      (node (ref "R28") (pin "2") (pinfunction "2_2") (pintype "passive"))
      (node (ref "R29") (pin "2") (pinfunction "2_2") (pintype "passive"))
      (node (ref "R30") (pin "2") (pinfunction "2_2") (pintype "passive"))
      (node (ref "REFVSS") (pin "TP") (pinfunction "TP_TP") (pintype "input"))
      (node (ref "SL1") (pin "1") (pinfunction "1_1") (pintype "passive"))
      (node (ref "SL2") (pin "1") (pinfunction "1_1") (pintype "passive"))
      (node (ref "SL3") (pin "1") (pinfunction "1_1") (pintype "passive"))
      (node (ref "SL4") (pin "1") (pinfunction "1_1") (pintype "passive"))
      (node (ref "SPI_IN") (pin "8") (pinfunction "S_8") (pintype "passive"))
      (node (ref "SPI_OUT") (pin "8") (pinfunction "S_8") (pintype "passive"))
      (node (ref "U$1") (pin "GND") (pinfunction "GND_GND") (pintype "bidirectional"))
    )
    (net (code "94") (name "unconnected-(IC2-Pad2)") (class "Default")
      (node (ref "IC2") (pin "2") (pinfunction "2_2") (pintype "passive"))
    )
    (net (code "95") (name "unconnected-(IC2-Pad3)") (class "Default")
      (node (ref "IC2") (pin "3") (pinfunction "3_3") (pintype "passive"))
    )
    (net (code "96") (name "unconnected-(IC2-Pad4)") (class "Default")
      (node (ref "IC2") (pin "4") (pinfunction "4_4") (pintype "passive"))
    )
    (net (code "97") (name "unconnected-(IC3-OPT-Pad3)") (class "Default")
      (node (ref "IC3") (pin "3") (pinfunction "OPT_3") (pintype "output"))
    )
    (net (code "98") (name "unconnected-(IC3-TRM-Pad5)") (class "Default")
      (node (ref "IC3") (pin "5") (pinfunction "TRM_5") (pintype "input"))
    )
    (net (code "99") (name "unconnected-(P-AH-S-Pad7)") (class "Default")
      (node (ref "P-A") (pin "7") (pinfunction "S_7") (pintype "passive"))
    )
  )
)
